# 07-1G_Phy1.net
KiCad netlist of a schematic drawn in Altium Designer
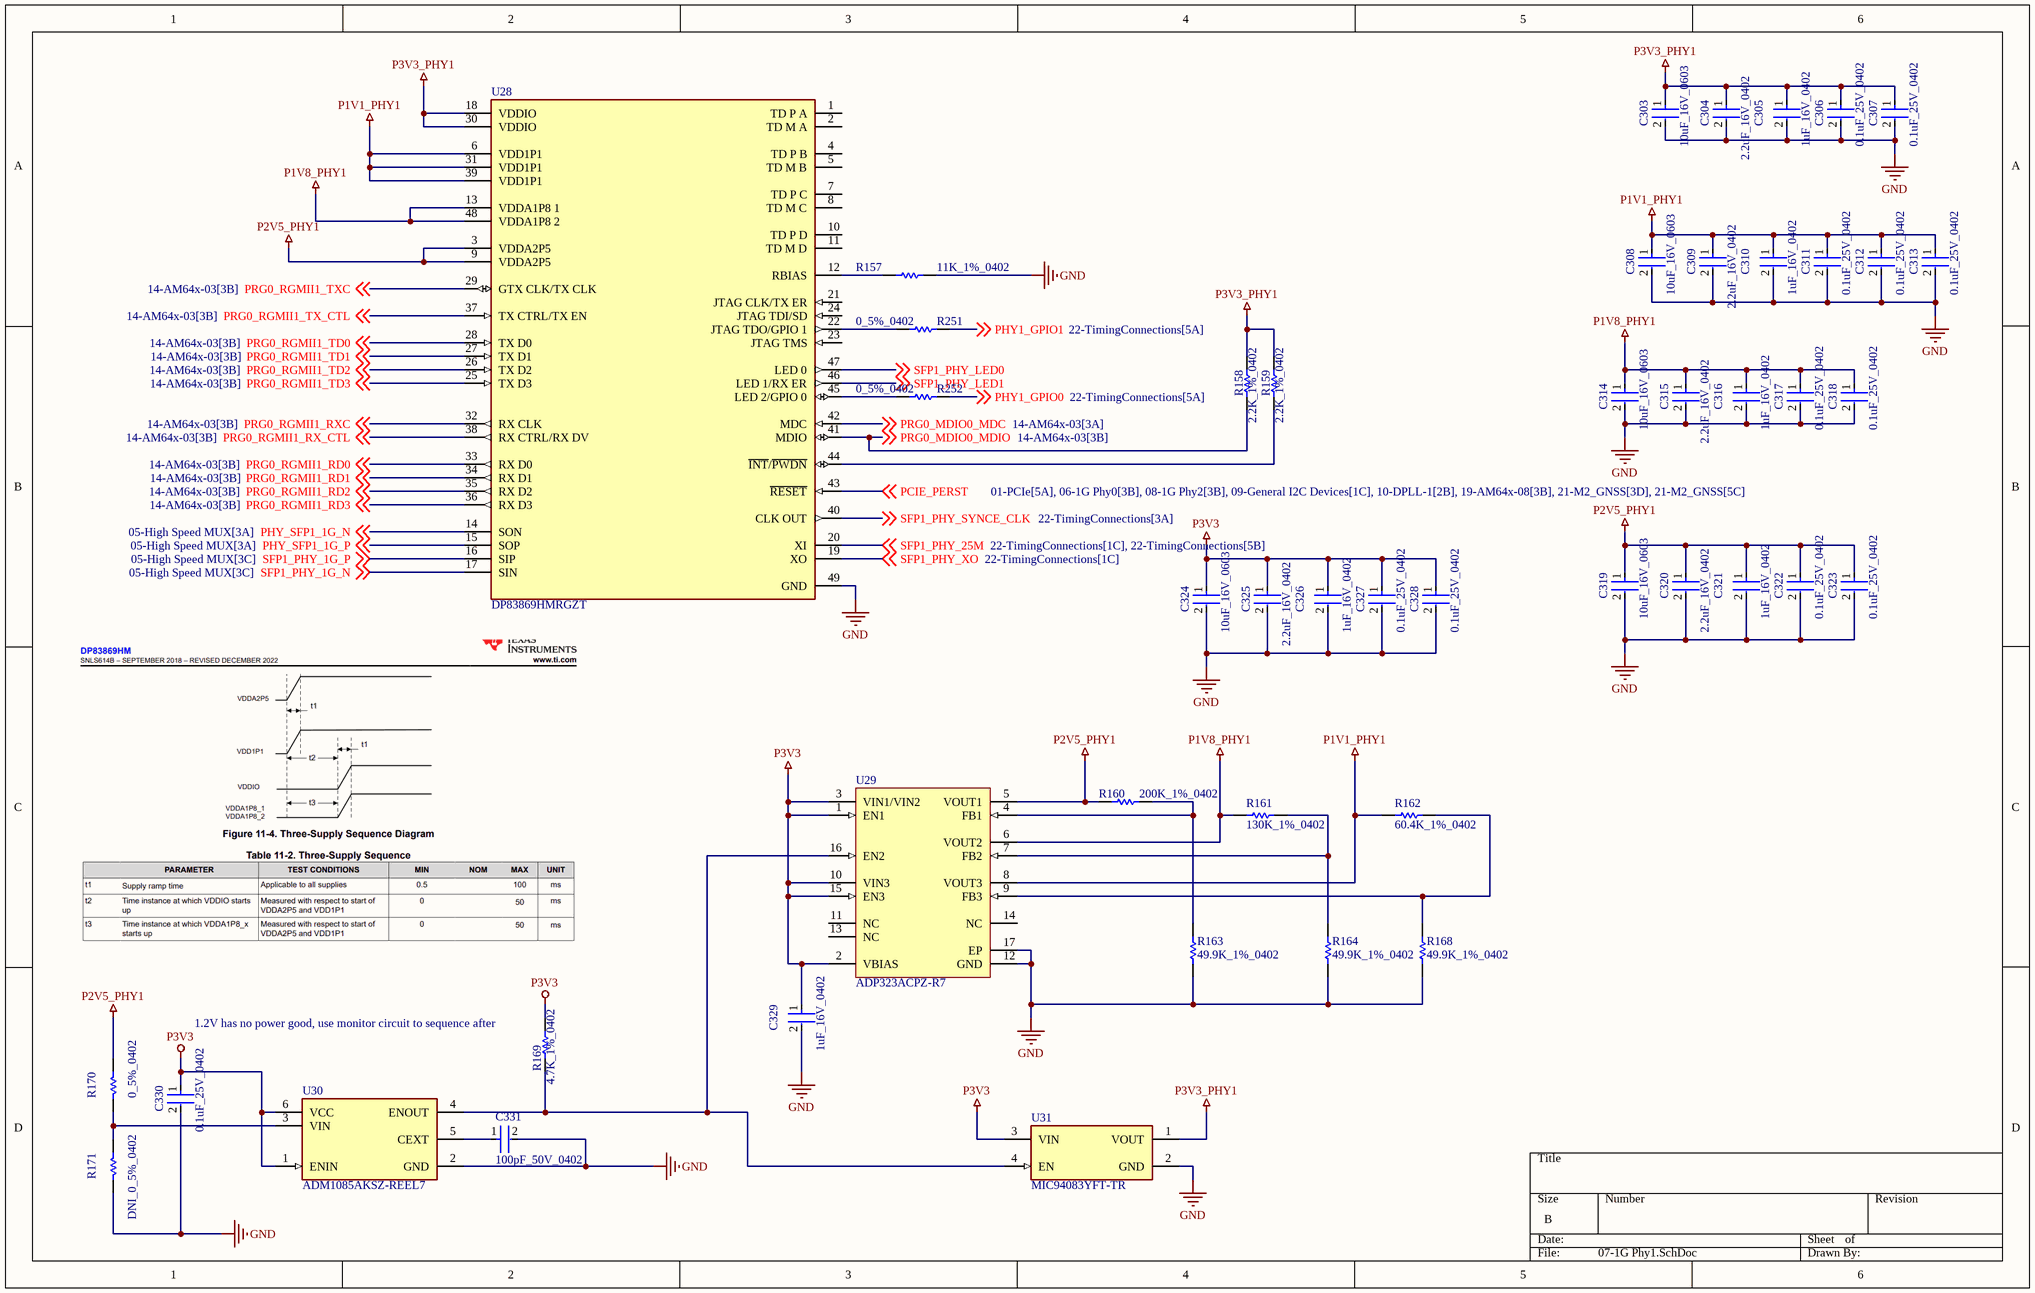
[diagram p0: 07-1G Phy1.SchDoc]

(export (version "E")
  (design (tool "Eeschema 10.0.6"))
  (components
    (comp (ref "C303")
      (value "10uF_16V_0603")
      (footprint "FP-0603-L_1_6_0_2-W_0_8_0-MFG")
      (description "Multilayer Ceramic Capacitor 10uF 16V X5R 20% SMD 0603 T/R")
      (fields (field (name "TOLERANCE") "20%"))
      (libsource (lib "Altium Content Vault") (part "b4654b650e69147ec39a6b967a45e02"))
    )
    (comp (ref "C304")
      (value "2.2uF_16V_0402")
      (footprint "FP-C1005-050-0_05-IPC_A")
      (description "Multilayer Ceramic Capacitors 2.2μF ±10% 16V X5R SMD 0402")
      (fields (field (name "TOLERANCE") "10%"))
      (libsource (lib "Altium Content Vault") (part "b4654b650e69147ec39a6b967a45e02"))
    )
    (comp (ref "C305")
      (value "1uF_16V_0402")
      (footprint "FP-0402-L_1_0_0_05-W_0_5-IPC_A")
      (description "None")
      (fields (field (name "TOLERANCE") "10%"))
      (libsource (lib "Altium Content Vault") (part "b4654b650e69147ec39a6b967a45e02"))
    )
    (comp (ref "C306")
      (value "0.1uF_25V_0402")
      (footprint "FP-0402-L_1_0_1-W_0_5_0_1-IPC_C")
      (description "General Purpose Ceramic Capacitor, 0402, 100nF, 10%, X7R, 15%, 25V")
      (fields (field (name "VOLTAGE") "25V") (field (name "TOLERANCE") "10%"))
      (libsource (lib "Altium Content Vault") (part "b4654b650e69147ec39a6b967a45e02"))
    )
    (comp (ref "C307")
      (value "0.1uF_25V_0402")
      (footprint "FP-0402-L_1_0_1-W_0_5_0_1-IPC_C")
      (description "General Purpose Ceramic Capacitor, 0402, 100nF, 10%, X7R, 15%, 25V")
      (fields (field (name "VOLTAGE") "25V") (field (name "TOLERANCE") "10%"))
      (libsource (lib "Altium Content Vault") (part "b4654b650e69147ec39a6b967a45e02"))
    )
    (comp (ref "C308")
      (value "10uF_16V_0603")
      (footprint "FP-0603-L_1_6_0_2-W_0_8_0-MFG")
      (description "Multilayer Ceramic Capacitor 10uF 16V X5R 20% SMD 0603 T/R")
      (fields (field (name "TOLERANCE") "20%"))
      (libsource (lib "Altium Content Vault") (part "b4654b650e69147ec39a6b967a45e02"))
    )
    (comp (ref "C309")
      (value "2.2uF_16V_0402")
      (footprint "FP-C1005-050-0_05-IPC_A")
      (description "Multilayer Ceramic Capacitors 2.2μF ±10% 16V X5R SMD 0402")
      (fields (field (name "TOLERANCE") "10%"))
      (libsource (lib "Altium Content Vault") (part "b4654b650e69147ec39a6b967a45e02"))
    )
    (comp (ref "C310")
      (value "1uF_16V_0402")
      (footprint "FP-0402-L_1_0_0_05-W_0_5-IPC_A")
      (description "None")
      (fields (field (name "TOLERANCE") "10%"))
      (libsource (lib "Altium Content Vault") (part "b4654b650e69147ec39a6b967a45e02"))
    )
    (comp (ref "C311")
      (value "0.1uF_25V_0402")
      (footprint "FP-0402-L_1_0_1-W_0_5_0_1-IPC_C")
      (description "General Purpose Ceramic Capacitor, 0402, 100nF, 10%, X7R, 15%, 25V")
      (fields (field (name "VOLTAGE") "25V") (field (name "TOLERANCE") "10%"))
      (libsource (lib "Altium Content Vault") (part "b4654b650e69147ec39a6b967a45e02"))
    )
    (comp (ref "C312")
      (value "0.1uF_25V_0402")
      (footprint "FP-0402-L_1_0_1-W_0_5_0_1-IPC_C")
      (description "General Purpose Ceramic Capacitor, 0402, 100nF, 10%, X7R, 15%, 25V")
      (fields (field (name "VOLTAGE") "25V") (field (name "TOLERANCE") "10%"))
      (libsource (lib "Altium Content Vault") (part "b4654b650e69147ec39a6b967a45e02"))
    )
    (comp (ref "C313")
      (value "0.1uF_25V_0402")
      (footprint "FP-0402-L_1_0_1-W_0_5_0_1-IPC_C")
      (description "General Purpose Ceramic Capacitor, 0402, 100nF, 10%, X7R, 15%, 25V")
      (fields (field (name "VOLTAGE") "25V") (field (name "TOLERANCE") "10%"))
      (libsource (lib "Altium Content Vault") (part "b4654b650e69147ec39a6b967a45e02"))
    )
    (comp (ref "C314")
      (value "10uF_16V_0603")
      (footprint "FP-0603-L_1_6_0_2-W_0_8_0-MFG")
      (description "Multilayer Ceramic Capacitor 10uF 16V X5R 20% SMD 0603 T/R")
      (fields (field (name "TOLERANCE") "20%"))
      (libsource (lib "Altium Content Vault") (part "b4654b650e69147ec39a6b967a45e02"))
    )
    (comp (ref "C315")
      (value "2.2uF_16V_0402")
      (footprint "FP-C1005-050-0_05-IPC_A")
      (description "Multilayer Ceramic Capacitors 2.2μF ±10% 16V X5R SMD 0402")
      (fields (field (name "TOLERANCE") "10%"))
      (libsource (lib "Altium Content Vault") (part "b4654b650e69147ec39a6b967a45e02"))
    )
    (comp (ref "C316")
      (value "1uF_16V_0402")
      (footprint "FP-0402-L_1_0_0_05-W_0_5-IPC_A")
      (description "None")
      (fields (field (name "TOLERANCE") "10%"))
      (libsource (lib "Altium Content Vault") (part "b4654b650e69147ec39a6b967a45e02"))
    )
    (comp (ref "C317")
      (value "0.1uF_25V_0402")
      (footprint "FP-0402-L_1_0_1-W_0_5_0_1-IPC_C")
      (description "General Purpose Ceramic Capacitor, 0402, 100nF, 10%, X7R, 15%, 25V")
      (fields (field (name "VOLTAGE") "25V") (field (name "TOLERANCE") "10%"))
      (libsource (lib "Altium Content Vault") (part "b4654b650e69147ec39a6b967a45e02"))
    )
    (comp (ref "C318")
      (value "0.1uF_25V_0402")
      (footprint "FP-0402-L_1_0_1-W_0_5_0_1-IPC_C")
      (description "General Purpose Ceramic Capacitor, 0402, 100nF, 10%, X7R, 15%, 25V")
      (fields (field (name "VOLTAGE") "25V") (field (name "TOLERANCE") "10%"))
      (libsource (lib "Altium Content Vault") (part "b4654b650e69147ec39a6b967a45e02"))
    )
    (comp (ref "C319")
      (value "10uF_16V_0603")
      (footprint "FP-0603-L_1_6_0_2-W_0_8_0-MFG")
      (description "Multilayer Ceramic Capacitor 10uF 16V X5R 20% SMD 0603 T/R")
      (fields (field (name "TOLERANCE") "20%"))
      (libsource (lib "Altium Content Vault") (part "b4654b650e69147ec39a6b967a45e02"))
    )
    (comp (ref "C320")
      (value "2.2uF_16V_0402")
      (footprint "FP-C1005-050-0_05-IPC_A")
      (description "Multilayer Ceramic Capacitors 2.2μF ±10% 16V X5R SMD 0402")
      (fields (field (name "TOLERANCE") "10%"))
      (libsource (lib "Altium Content Vault") (part "b4654b650e69147ec39a6b967a45e02"))
    )
    (comp (ref "C321")
      (value "1uF_16V_0402")
      (footprint "FP-0402-L_1_0_0_05-W_0_5-IPC_A")
      (description "None")
      (fields (field (name "TOLERANCE") "10%"))
      (libsource (lib "Altium Content Vault") (part "b4654b650e69147ec39a6b967a45e02"))
    )
    (comp (ref "C322")
      (value "0.1uF_25V_0402")
      (footprint "FP-0402-L_1_0_1-W_0_5_0_1-IPC_C")
      (description "General Purpose Ceramic Capacitor, 0402, 100nF, 10%, X7R, 15%, 25V")
      (fields (field (name "VOLTAGE") "25V") (field (name "TOLERANCE") "10%"))
      (libsource (lib "Altium Content Vault") (part "b4654b650e69147ec39a6b967a45e02"))
    )
    (comp (ref "C323")
      (value "0.1uF_25V_0402")
      (footprint "FP-0402-L_1_0_1-W_0_5_0_1-IPC_C")
      (description "General Purpose Ceramic Capacitor, 0402, 100nF, 10%, X7R, 15%, 25V")
      (fields (field (name "VOLTAGE") "25V") (field (name "TOLERANCE") "10%"))
      (libsource (lib "Altium Content Vault") (part "b4654b650e69147ec39a6b967a45e02"))
    )
    (comp (ref "C324")
      (value "10uF_16V_0603")
      (footprint "FP-0603-L_1_6_0_2-W_0_8_0-MFG")
      (description "Multilayer Ceramic Capacitor 10uF 16V X5R 20% SMD 0603 T/R")
      (fields (field (name "TOLERANCE") "20%"))
      (libsource (lib "Altium Content Vault") (part "b4654b650e69147ec39a6b967a45e02"))
    )
    (comp (ref "C325")
      (value "2.2uF_16V_0402")
      (footprint "FP-C1005-050-0_05-IPC_A")
      (description "Multilayer Ceramic Capacitors 2.2μF ±10% 16V X5R SMD 0402")
      (fields (field (name "TOLERANCE") "10%"))
      (libsource (lib "Altium Content Vault") (part "b4654b650e69147ec39a6b967a45e02"))
    )
    (comp (ref "C326")
      (value "1uF_16V_0402")
      (footprint "FP-0402-L_1_0_0_05-W_0_5-IPC_A")
      (description "None")
      (fields (field (name "TOLERANCE") "10%"))
      (libsource (lib "Altium Content Vault") (part "b4654b650e69147ec39a6b967a45e02"))
    )
    (comp (ref "C327")
      (value "0.1uF_25V_0402")
      (footprint "FP-0402-L_1_0_1-W_0_5_0_1-IPC_C")
      (description "General Purpose Ceramic Capacitor, 0402, 100nF, 10%, X7R, 15%, 25V")
      (fields (field (name "VOLTAGE") "25V") (field (name "TOLERANCE") "10%"))
      (libsource (lib "Altium Content Vault") (part "b4654b650e69147ec39a6b967a45e02"))
    )
    (comp (ref "C328")
      (value "0.1uF_25V_0402")
      (footprint "FP-0402-L_1_0_1-W_0_5_0_1-IPC_C")
      (description "General Purpose Ceramic Capacitor, 0402, 100nF, 10%, X7R, 15%, 25V")
      (fields (field (name "VOLTAGE") "25V") (field (name "TOLERANCE") "10%"))
      (libsource (lib "Altium Content Vault") (part "b4654b650e69147ec39a6b967a45e02"))
    )
    (comp (ref "C329")
      (value "1uF_16V_0402")
      (footprint "FP-0402-L_1_0_0_05-W_0_5-IPC_A")
      (description "None")
      (fields (field (name "TOLERANCE") "10%"))
      (libsource (lib "Altium Content Vault") (part "b4654b650e69147ec39a6b967a45e02"))
    )
    (comp (ref "C330")
      (value "0.1uF_25V_0402")
      (footprint "FP-0402-L_1_0_1-W_0_5_0_1-IPC_C")
      (description "General Purpose Ceramic Capacitor, 0402, 100nF, 10%, X7R, 15%, 25V")
      (fields (field (name "VOLTAGE") "25V") (field (name "TOLERANCE") "10%"))
      (libsource (lib "Altium Content Vault") (part "b4654b650e69147ec39a6b967a45e02"))
    )
    (comp (ref "C331")
      (value "100pF_50V_0402")
      (footprint "FP-C0402-BB-MFG")
      (description "CAP CER 100PF 50V C0G/NP0 0402")
      (fields (field (name "TOLERANCE") "0.02") (field (name "MANUFACTURER") "Kemet"))
      (libsource (lib "Altium Content Vault") (part "b4654b650e69147ec39a6b967a45e02"))
    )
    (comp (ref "R157")
      (value "11K_1%_0402")
      (footprint "RESC1005X40X25LL05T10")
      (fields (field (name "MANUFACTURER") "Yageo / Phycomp") (field (name "PART NUMBER") "RC0402FR-0711KL"))
      (libsource (lib "Altium Content Vault") (part "RES"))
    )
    (comp (ref "R158")
      (value "2.2K_1%_0402")
      (footprint "RESC1005X40X25ML10T10")
      (fields (field (name "PART NUMBER") "MC00625W040212K2") (field (name "MANUFACTURER") "Multicomp"))
      (libsource (lib "Altium Content Vault") (part "RES"))
    )
    (comp (ref "R159")
      (value "2.2K_1%_0402")
      (footprint "RESC1005X40X25ML10T10")
      (fields (field (name "PART NUMBER") "MC00625W040212K2") (field (name "MANUFACTURER") "Multicomp"))
      (libsource (lib "Altium Content Vault") (part "RES"))
    )
    (comp (ref "R160")
      (value "200K_1%_0402")
      (footprint "RESC1005X40X25LL10T10")
      (fields (field (name "PART NUMBER") "CR0402-FX-2003GLF") (field (name "MANUFACTURER") "Bourns"))
      (libsource (lib "Altium Content Vault") (part "RES"))
    )
    (comp (ref "R161")
      (value "130K_1%_0402")
      (footprint "RESC1005X40X25NL10T10")
      (fields
        (field (name "PART NUMBER") "CRG0402F130K")
        (field (name "MANUFACTURER") "TE Connectivity / AMP")
      )
      (libsource (lib "Altium Content Vault") (part "RES"))
    )
    (comp (ref "R162")
      (value "60.4K_1%_0402")
      (footprint "RESC1005X40X25LL05T10")
      (fields (field (name "MANUFACTURER") "Yageo / Phycomp") (field (name "PART NUMBER") "RC0402FR-0760K4L"))
      (libsource (lib "Altium Content Vault") (part "RES"))
    )
    (comp (ref "R163")
      (value "49.9K_1%_0402")
      (footprint "RESC1005X40X25LL10T10")
      (fields (field (name "MANUFACTURER") "Bourns") (field (name "PART NUMBER") "CR0402-FX-4992GLF"))
      (libsource (lib "Altium Content Vault") (part "RES"))
    )
    (comp (ref "R164")
      (value "49.9K_1%_0402")
      (footprint "RESC1005X40X25LL10T10")
      (fields (field (name "MANUFACTURER") "Bourns") (field (name "PART NUMBER") "CR0402-FX-4992GLF"))
      (libsource (lib "Altium Content Vault") (part "RES"))
    )
    (comp (ref "R168")
      (value "49.9K_1%_0402")
      (footprint "RESC1005X40X25LL10T10")
      (fields (field (name "MANUFACTURER") "Bourns") (field (name "PART NUMBER") "CR0402-FX-4992GLF"))
      (libsource (lib "Altium Content Vault") (part "RES"))
    )
    (comp (ref "R169")
      (value "4.7K_1%_0402")
      (footprint "RESC1005X40X25NL10T10")
      (fields (field (name "MANUFACTURER") "Bourns") (field (name "PART NUMBER") "CR0402-FX-4701GLF"))
      (libsource (lib "Altium Content Vault") (part "RES"))
    )
    (comp (ref "R170")
      (value "0_5%_0402")
      (footprint "RESC1005X40X25LL10T10")
      (fields (field (name "MANUFACTURER") "KOA Speer") (field (name "PART NUMBER") "RK73Z1ETTP"))
      (libsource (lib "Altium Content Vault") (part "RES"))
    )
    (comp (ref "R171")
      (value "DNI_0_5%_0402")
      (footprint "RESC1005X40X25LL10T10")
      (fields (field (name "MANUFACTURER") "KOA Speer") (field (name "PART NUMBER") "RK73Z1ETTP"))
      (libsource (lib "Altium Content Vault") (part "RES"))
    )
    (comp (ref "R251")
      (value "0_5%_0402")
      (footprint "RESC1005X40X25LL10T10")
      (fields (field (name "MANUFACTURER") "KOA Speer") (field (name "PART NUMBER") "RK73Z1ETTP"))
      (libsource (lib "Altium Content Vault") (part "RES"))
    )
    (comp (ref "R252")
      (value "0_5%_0402")
      (footprint "RESC1005X40X25LL10T10")
      (fields (field (name "MANUFACTURER") "KOA Speer") (field (name "PART NUMBER") "RK73Z1ETTP"))
      (libsource (lib "Altium Content Vault") (part "RES"))
    )
    (comp (ref "U28")
      (value "DP83869HMRGZT")
      (footprint "FP-RGZ0048B-IPC_A")
      (description "IC TRANSCEIVER 1/1 48FN")
      (libsource (lib "Altium Content Vault") (part "90cc30aaca705ff2adc2433a1cc0005"))
    )
    (comp (ref "U29")
      (value "ADP323ACPZ-R7")
      (footprint "ADI-CP-16-27_N")
      (fields (field (name "MANUFACTURER") "Analog Devices"))
      (libsource (lib "Altium Content Vault") (part "ADI-ADP323-CP-16-27"))
    )
    (comp (ref "U30")
      (value "ADM1085AKSZ-REEL7")
      (footprint "FP-KS-6-IPC_B")
      (description "IC SUPERVISOR 1 CHANNEL SC70-6")
      (libsource (lib "Altium Content Vault") (part "4d0b74b7e8e8a1541abc8f47282371d"))
    )
    (comp (ref "U31")
      (value "MIC94083YFT-TR")
      (footprint "FP-FTDFN085085-4LD-PL-1-MFG")
      (description "IC PWR SWITCH P-CHAN 1:1 4TMLF")
      (libsource (lib "Altium Content Vault") (part "f982b0e4379ad1be1c154354d61e319"))
    )
  )
  (nets
    (net (code "1") (name "GND") (class "Default")
      (node (ref "C303") (pin "2") (pinfunction "2_2") (pintype "passive"))
      (node (ref "C304") (pin "2") (pinfunction "2_2") (pintype "passive"))
      (node (ref "C305") (pin "2") (pinfunction "2_2") (pintype "passive"))
      (node (ref "C306") (pin "2") (pinfunction "2_2") (pintype "passive"))
      (node (ref "C307") (pin "2") (pinfunction "2_2") (pintype "passive"))
      (node (ref "C308") (pin "2") (pinfunction "2_2") (pintype "passive"))
      (node (ref "C309") (pin "2") (pinfunction "2_2") (pintype "passive"))
      (node (ref "C310") (pin "2") (pinfunction "2_2") (pintype "passive"))
      (node (ref "C311") (pin "2") (pinfunction "2_2") (pintype "passive"))
      (node (ref "C312") (pin "2") (pinfunction "2_2") (pintype "passive"))
      (node (ref "C313") (pin "2") (pinfunction "2_2") (pintype "passive"))
      (node (ref "C314") (pin "2") (pinfunction "2_2") (pintype "passive"))
      (node (ref "C315") (pin "2") (pinfunction "2_2") (pintype "passive"))
      (node (ref "C316") (pin "2") (pinfunction "2_2") (pintype "passive"))
      (node (ref "C317") (pin "2") (pinfunction "2_2") (pintype "passive"))
      (node (ref "C318") (pin "2") (pinfunction "2_2") (pintype "passive"))
      (node (ref "C319") (pin "2") (pinfunction "2_2") (pintype "passive"))
      (node (ref "C320") (pin "2") (pinfunction "2_2") (pintype "passive"))
      (node (ref "C321") (pin "2") (pinfunction "2_2") (pintype "passive"))
      (node (ref "C322") (pin "2") (pinfunction "2_2") (pintype "passive"))
      (node (ref "C323") (pin "2") (pinfunction "2_2") (pintype "passive"))
      (node (ref "C324") (pin "2") (pinfunction "2_2") (pintype "passive"))
      (node (ref "C325") (pin "2") (pinfunction "2_2") (pintype "passive"))
      (node (ref "C326") (pin "2") (pinfunction "2_2") (pintype "passive"))
      (node (ref "C327") (pin "2") (pinfunction "2_2") (pintype "passive"))
      (node (ref "C328") (pin "2") (pinfunction "2_2") (pintype "passive"))
      (node (ref "C329") (pin "2") (pinfunction "2_2") (pintype "passive"))
      (node (ref "C330") (pin "2") (pinfunction "2_2") (pintype "passive"))
      (node (ref "C331") (pin "2") (pinfunction "2_2") (pintype "passive"))
      (node (ref "R157") (pin "2") (pinfunction "2_2") (pintype "passive"))
      (node (ref "R163") (pin "1") (pinfunction "1_1") (pintype "passive"))
      (node (ref "R164") (pin "1") (pinfunction "1_1") (pintype "passive"))
      (node (ref "R168") (pin "1") (pinfunction "1_1") (pintype "passive"))
      (node (ref "R171") (pin "2") (pinfunction "2_2") (pintype "passive"))
      (node (ref "U28") (pin "49") (pinfunction "GND_49") (pintype "power_in"))
      (node (ref "U29") (pin "12") (pinfunction "GND_12") (pintype "power_in"))
      (node (ref "U29") (pin "17") (pinfunction "EP_17") (pintype "power_in"))
      (node (ref "U30") (pin "2") (pinfunction "GND_2") (pintype "power_in"))
      (node (ref "U31") (pin "2") (pinfunction "GND_2") (pintype "power_in"))
    )
    (net (code "2") (name "Net-(U28-JTAG_TDO{slash}GPIO_1)") (class "Default")
      (node (ref "R251") (pin "1") (pinfunction "1_1") (pintype "passive"))
      (node (ref "U28") (pin "22") (pinfunction "JTAG_TDO/GPIO_1_22") (pintype "output"))
    )
    (net (code "3") (name "Net-(U28-LED_2{slash}GPIO_0)") (class "Default")
      (node (ref "R252") (pin "1") (pinfunction "1_1") (pintype "passive"))
      (node (ref "U28") (pin "45") (pinfunction "LED_2/GPIO_0_45") (pintype "bidirectional"))
    )
    (net (code "4") (name "Net-(U28-RBIAS)") (class "Default")
      (node (ref "R157") (pin "1") (pinfunction "1_1") (pintype "passive"))
      (node (ref "U28") (pin "12") (pinfunction "RBIAS_12") (pintype "passive"))
    )
    (net (code "5") (name "Net-(U28-~{INT}{slash}~{PWDN})") (class "Default")
      (node (ref "R159") (pin "1") (pinfunction "1_1") (pintype "passive"))
      (node (ref "U28") (pin "44") (pinfunction "~{INT}/~{PWDN}_44") (pintype "bidirectional"))
    )
    (net (code "6") (name "Net-(U29-EN2)") (class "Default")
      (node (ref "R169") (pin "2") (pinfunction "2_2") (pintype "passive"))
      (node (ref "U29") (pin "16") (pinfunction "EN2_16") (pintype "input"))
      (node (ref "U30") (pin "4") (pinfunction "ENOUT_4") (pintype "open_collector"))
      (node (ref "U31") (pin "4") (pinfunction "EN_4") (pintype "input"))
    )
    (net (code "7") (name "Net-(U29-FB1)") (class "Default")
      (node (ref "R160") (pin "2") (pinfunction "2_2") (pintype "passive"))
      (node (ref "R163") (pin "2") (pinfunction "2_2") (pintype "passive"))
      (node (ref "U29") (pin "4") (pinfunction "FB1_4") (pintype "input"))
    )
    (net (code "8") (name "Net-(U29-FB2)") (class "Default")
      (node (ref "R161") (pin "2") (pinfunction "2_2") (pintype "passive"))
      (node (ref "R164") (pin "2") (pinfunction "2_2") (pintype "passive"))
      (node (ref "U29") (pin "7") (pinfunction "FB2_7") (pintype "input"))
    )
    (net (code "9") (name "Net-(U29-FB3)") (class "Default")
      (node (ref "R162") (pin "2") (pinfunction "2_2") (pintype "passive"))
      (node (ref "R168") (pin "2") (pinfunction "2_2") (pintype "passive"))
      (node (ref "U29") (pin "9") (pinfunction "FB3_9") (pintype "input"))
    )
    (net (code "10") (name "Net-(U30-CEXT)") (class "Default")
      (node (ref "C331") (pin "1") (pinfunction "1_1") (pintype "passive"))
      (node (ref "U30") (pin "5") (pinfunction "CEXT_5") (pintype "passive"))
    )
    (net (code "11") (name "Net-(U30-VIN)") (class "Default")
      (node (ref "R170") (pin "2") (pinfunction "2_2") (pintype "passive"))
      (node (ref "R171") (pin "1") (pinfunction "1_1") (pintype "passive"))
      (node (ref "U30") (pin "3") (pinfunction "VIN_3") (pintype "power_in"))
    )
    (net (code "12") (name "P1V1_PHY1") (class "Default")
      (node (ref "C308") (pin "1") (pinfunction "1_1") (pintype "passive"))
      (node (ref "C309") (pin "1") (pinfunction "1_1") (pintype "passive"))
      (node (ref "C310") (pin "1") (pinfunction "1_1") (pintype "passive"))
      (node (ref "C311") (pin "1") (pinfunction "1_1") (pintype "passive"))
      (node (ref "C312") (pin "1") (pinfunction "1_1") (pintype "passive"))
      (node (ref "C313") (pin "1") (pinfunction "1_1") (pintype "passive"))
      (node (ref "R162") (pin "1") (pinfunction "1_1") (pintype "passive"))
      (node (ref "U28") (pin "31") (pinfunction "VDD1P1_31") (pintype "power_in"))
      (node (ref "U28") (pin "39") (pinfunction "VDD1P1_39") (pintype "power_in"))
      (node (ref "U28") (pin "6") (pinfunction "VDD1P1_6") (pintype "power_in"))
      (node (ref "U29") (pin "8") (pinfunction "VOUT3_8") (pintype "power_in"))
    )
    (net (code "13") (name "P1V8_PHY1") (class "Default")
      (node (ref "C314") (pin "1") (pinfunction "1_1") (pintype "passive"))
      (node (ref "C315") (pin "1") (pinfunction "1_1") (pintype "passive"))
      (node (ref "C316") (pin "1") (pinfunction "1_1") (pintype "passive"))
      (node (ref "C317") (pin "1") (pinfunction "1_1") (pintype "passive"))
      (node (ref "C318") (pin "1") (pinfunction "1_1") (pintype "passive"))
      (node (ref "R161") (pin "1") (pinfunction "1_1") (pintype "passive"))
      (node (ref "U28") (pin "13") (pinfunction "VDDA1P8_1_13") (pintype "power_in"))
      (node (ref "U28") (pin "48") (pinfunction "VDDA1P8_2_48") (pintype "power_in"))
      (node (ref "U29") (pin "6") (pinfunction "VOUT2_6") (pintype "power_in"))
    )
    (net (code "14") (name "P2V5_PHY1") (class "Default")
      (node (ref "C319") (pin "1") (pinfunction "1_1") (pintype "passive"))
      (node (ref "C320") (pin "1") (pinfunction "1_1") (pintype "passive"))
      (node (ref "C321") (pin "1") (pinfunction "1_1") (pintype "passive"))
      (node (ref "C322") (pin "1") (pinfunction "1_1") (pintype "passive"))
      (node (ref "C323") (pin "1") (pinfunction "1_1") (pintype "passive"))
      (node (ref "R160") (pin "1") (pinfunction "1_1") (pintype "passive"))
      (node (ref "R170") (pin "1") (pinfunction "1_1") (pintype "passive"))
      (node (ref "U28") (pin "3") (pinfunction "VDDA2P5_3") (pintype "power_in"))
      (node (ref "U28") (pin "9") (pinfunction "VDDA2P5_9") (pintype "power_in"))
      (node (ref "U29") (pin "5") (pinfunction "VOUT1_5") (pintype "power_in"))
    )
    (net (code "15") (name "P3V3") (class "Default")
      (node (ref "C324") (pin "1") (pinfunction "1_1") (pintype "passive"))
      (node (ref "C325") (pin "1") (pinfunction "1_1") (pintype "passive"))
      (node (ref "C326") (pin "1") (pinfunction "1_1") (pintype "passive"))
      (node (ref "C327") (pin "1") (pinfunction "1_1") (pintype "passive"))
      (node (ref "C328") (pin "1") (pinfunction "1_1") (pintype "passive"))
      (node (ref "C329") (pin "1") (pinfunction "1_1") (pintype "passive"))
      (node (ref "C330") (pin "1") (pinfunction "1_1") (pintype "passive"))
      (node (ref "R169") (pin "1") (pinfunction "1_1") (pintype "passive"))
      (node (ref "U29") (pin "1") (pinfunction "EN1_1") (pintype "input"))
      (node (ref "U29") (pin "10") (pinfunction "VIN3_10") (pintype "power_in"))
      (node (ref "U29") (pin "15") (pinfunction "EN3_15") (pintype "input"))
      (node (ref "U29") (pin "2") (pinfunction "VBIAS_2") (pintype "power_in"))
      (node (ref "U29") (pin "3") (pinfunction "VIN1/VIN2_3") (pintype "power_in"))
      (node (ref "U30") (pin "1") (pinfunction "ENIN_1") (pintype "input"))
      (node (ref "U30") (pin "6") (pinfunction "VCC_6") (pintype "power_in"))
      (node (ref "U31") (pin "3") (pinfunction "VIN_3") (pintype "power_in"))
    )
    (net (code "16") (name "P3V3_PHY1") (class "Default")
      (node (ref "C303") (pin "1") (pinfunction "1_1") (pintype "passive"))
      (node (ref "C304") (pin "1") (pinfunction "1_1") (pintype "passive"))
      (node (ref "C305") (pin "1") (pinfunction "1_1") (pintype "passive"))
      (node (ref "C306") (pin "1") (pinfunction "1_1") (pintype "passive"))
      (node (ref "C307") (pin "1") (pinfunction "1_1") (pintype "passive"))
      (node (ref "R158") (pin "2") (pinfunction "2_2") (pintype "passive"))
      (node (ref "R159") (pin "2") (pinfunction "2_2") (pintype "passive"))
      (node (ref "U28") (pin "18") (pinfunction "VDDIO_18") (pintype "power_in"))
      (node (ref "U28") (pin "30") (pinfunction "VDDIO_30") (pintype "power_in"))
      (node (ref "U31") (pin "1") (pinfunction "VOUT_1") (pintype "power_in"))
    )
    (net (code "17") (name "PCIE_PERST") (class "Default")
      (node (ref "U28") (pin "43") (pinfunction "~{RESET}_43") (pintype "input"))
    )
    (net (code "18") (name "PHY1_GPIO0") (class "Default")
      (node (ref "R252") (pin "2") (pinfunction "2_2") (pintype "passive"))
    )
    (net (code "19") (name "PHY1_GPIO1") (class "Default")
      (node (ref "R251") (pin "2") (pinfunction "2_2") (pintype "passive"))
    )
    (net (code "20") (name "PHY_SFP1_1G_N") (class "Default")
      (node (ref "U28") (pin "14") (pinfunction "SON_14") (pintype "passive"))
    )
    (net (code "21") (name "PHY_SFP1_1G_P") (class "Default")
      (node (ref "U28") (pin "15") (pinfunction "SOP_15") (pintype "passive"))
    )
    (net (code "22") (name "PRG0_MDIO0_MDC") (class "Default")
      (node (ref "U28") (pin "42") (pinfunction "MDC_42") (pintype "input"))
    )
    (net (code "23") (name "PRG0_MDIO0_MDIO") (class "Default")
      (node (ref "R158") (pin "1") (pinfunction "1_1") (pintype "passive"))
      (node (ref "U28") (pin "41") (pinfunction "MDIO_41") (pintype "bidirectional"))
    )
    (net (code "24") (name "PRG0_RGMII1_RD0") (class "Default")
      (node (ref "U28") (pin "33") (pinfunction "RX_D0_33") (pintype "output"))
    )
    (net (code "25") (name "PRG0_RGMII1_RD1") (class "Default")
      (node (ref "U28") (pin "34") (pinfunction "RX_D1_34") (pintype "output"))
    )
    (net (code "26") (name "PRG0_RGMII1_RD2") (class "Default")
      (node (ref "U28") (pin "35") (pinfunction "RX_D2_35") (pintype "output"))
    )
    (net (code "27") (name "PRG0_RGMII1_RD3") (class "Default")
      (node (ref "U28") (pin "36") (pinfunction "RX_D3_36") (pintype "output"))
    )
    (net (code "28") (name "PRG0_RGMII1_RXC") (class "Default")
      (node (ref "U28") (pin "32") (pinfunction "RX_CLK_32") (pintype "output"))
    )
    (net (code "29") (name "PRG0_RGMII1_RX_CTL") (class "Default")
      (node (ref "U28") (pin "38") (pinfunction "RX_CTRL/RX_DV_38") (pintype "output"))
    )
    (net (code "30") (name "PRG0_RGMII1_TD0") (class "Default")
      (node (ref "U28") (pin "28") (pinfunction "TX_D0_28") (pintype "input"))
    )
    (net (code "31") (name "PRG0_RGMII1_TD1") (class "Default")
      (node (ref "U28") (pin "27") (pinfunction "TX_D1_27") (pintype "input"))
    )
    (net (code "32") (name "PRG0_RGMII1_TD2") (class "Default")
      (node (ref "U28") (pin "26") (pinfunction "TX_D2_26") (pintype "input"))
    )
    (net (code "33") (name "PRG0_RGMII1_TD3") (class "Default")
      (node (ref "U28") (pin "25") (pinfunction "TX_D3_25") (pintype "input"))
    )
    (net (code "34") (name "PRG0_RGMII1_TXC") (class "Default")
      (node (ref "U28") (pin "29") (pinfunction "GTX_CLK/TX_CLK_29") (pintype "bidirectional"))
    )
    (net (code "35") (name "PRG0_RGMII1_TX_CTL") (class "Default")
      (node (ref "U28") (pin "37") (pinfunction "TX_CTRL/TX_EN_37") (pintype "input"))
    )
    (net (code "36") (name "SFP1_PHY_1G_N") (class "Default")
      (node (ref "U28") (pin "17") (pinfunction "SIN_17") (pintype "passive"))
    )
    (net (code "37") (name "SFP1_PHY_1G_P") (class "Default")
      (node (ref "U28") (pin "16") (pinfunction "SIP_16") (pintype "passive"))
    )
    (net (code "38") (name "SFP1_PHY_25M") (class "Default")
      (node (ref "U28") (pin "20") (pinfunction "XI_20") (pintype "passive"))
    )
    (net (code "39") (name "SFP1_PHY_LED0") (class "Default")
      (node (ref "U28") (pin "47") (pinfunction "LED_0_47") (pintype "output"))
    )
    (net (code "40") (name "SFP1_PHY_LED1") (class "Default")
      (node (ref "U28") (pin "46") (pinfunction "LED_1/RX_ER_46") (pintype "output"))
    )
    (net (code "41") (name "SFP1_PHY_SYNCE_CLK") (class "Default")
      (node (ref "U28") (pin "40") (pinfunction "CLK_OUT_40") (pintype "output"))
    )
    (net (code "42") (name "SFP1_PHY_XO") (class "Default")
      (node (ref "U28") (pin "19") (pinfunction "XO_19") (pintype "passive"))
    )
    (net (code "43") (name "unconnected-(U28-JTAG_CLK{slash}TX_ER-Pad21)") (class "Default")
      (node (ref "U28") (pin "21") (pinfunction "JTAG_CLK/TX_ER_21") (pintype "input"))
    )
    (net (code "44") (name "unconnected-(U28-JTAG_TDI{slash}SD-Pad24)") (class "Default")
      (node (ref "U28") (pin "24") (pinfunction "JTAG_TDI/SD_24") (pintype "input"))
    )
    (net (code "45") (name "unconnected-(U28-JTAG_TMS-Pad23)") (class "Default")
      (node (ref "U28") (pin "23") (pinfunction "JTAG_TMS_23") (pintype "input"))
    )
    (net (code "46") (name "unconnected-(U28-TD_M_A-Pad2)") (class "Default")
      (node (ref "U28") (pin "2") (pinfunction "TD_M_A_2") (pintype "passive"))
    )
    (net (code "47") (name "unconnected-(U28-TD_M_B-Pad5)") (class "Default")
      (node (ref "U28") (pin "5") (pinfunction "TD_M_B_5") (pintype "passive"))
    )
    (net (code "48") (name "unconnected-(U28-TD_M_C-Pad8)") (class "Default")
      (node (ref "U28") (pin "8") (pinfunction "TD_M_C_8") (pintype "passive"))
    )
    (net (code "49") (name "unconnected-(U28-TD_M_D-Pad11)") (class "Default")
      (node (ref "U28") (pin "11") (pinfunction "TD_M_D_11") (pintype "passive"))
    )
    (net (code "50") (name "unconnected-(U28-TD_P_A-Pad1)") (class "Default")
      (node (ref "U28") (pin "1") (pinfunction "TD_P_A_1") (pintype "passive"))
    )
    (net (code "51") (name "unconnected-(U28-TD_P_B-Pad4)") (class "Default")
      (node (ref "U28") (pin "4") (pinfunction "TD_P_B_4") (pintype "passive"))
    )
    (net (code "52") (name "unconnected-(U28-TD_P_C-Pad7)") (class "Default")
      (node (ref "U28") (pin "7") (pinfunction "TD_P_C_7") (pintype "passive"))
    )
    (net (code "53") (name "unconnected-(U28-TD_P_D-Pad10)") (class "Default")
      (node (ref "U28") (pin "10") (pinfunction "TD_P_D_10") (pintype "passive"))
    )
    (net (code "54") (name "unconnected-(U29-NC-Pad11)") (class "Default")
      (node (ref "U29") (pin "11") (pinfunction "NC_11") (pintype "passive"))
    )
    (net (code "55") (name "unconnected-(U29-NC-Pad13)") (class "Default")
      (node (ref "U29") (pin "13") (pinfunction "NC_13") (pintype "passive"))
    )
    (net (code "56") (name "unconnected-(U29-NC-Pad14)") (class "Default")
      (node (ref "U29") (pin "14") (pinfunction "NC_14") (pintype "passive"))
    )
  )
)
